# LPC55S69_MINI_B.net
KiCad netlist of a schematic drawn in Altium Designer
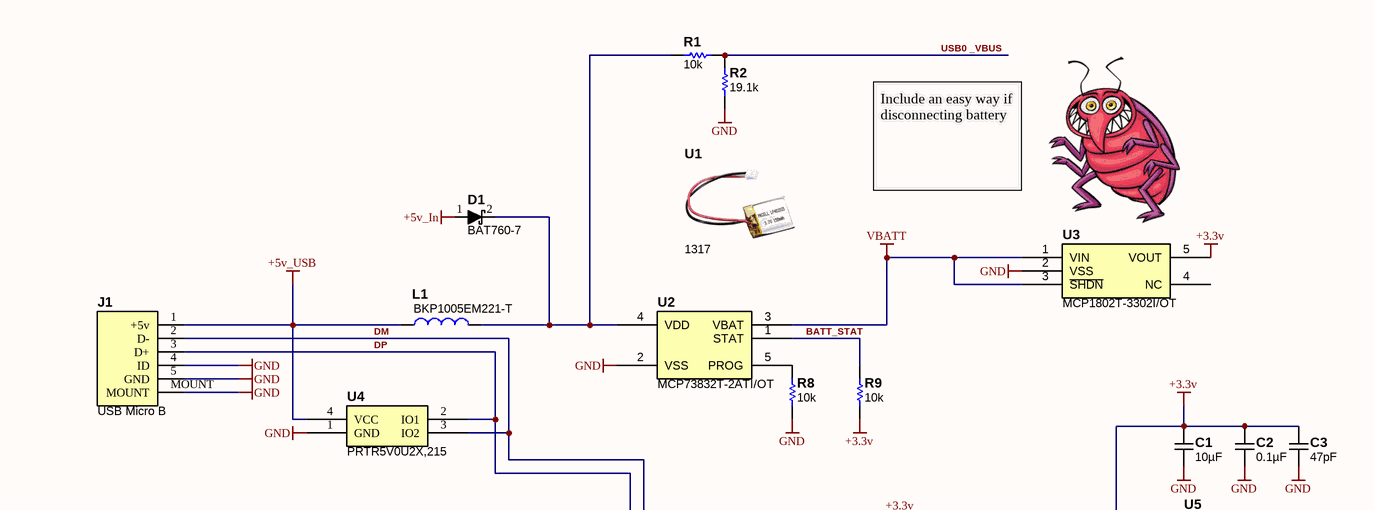
[diagram p0: LPC55S69_MINI [B].SchDoc, top left]
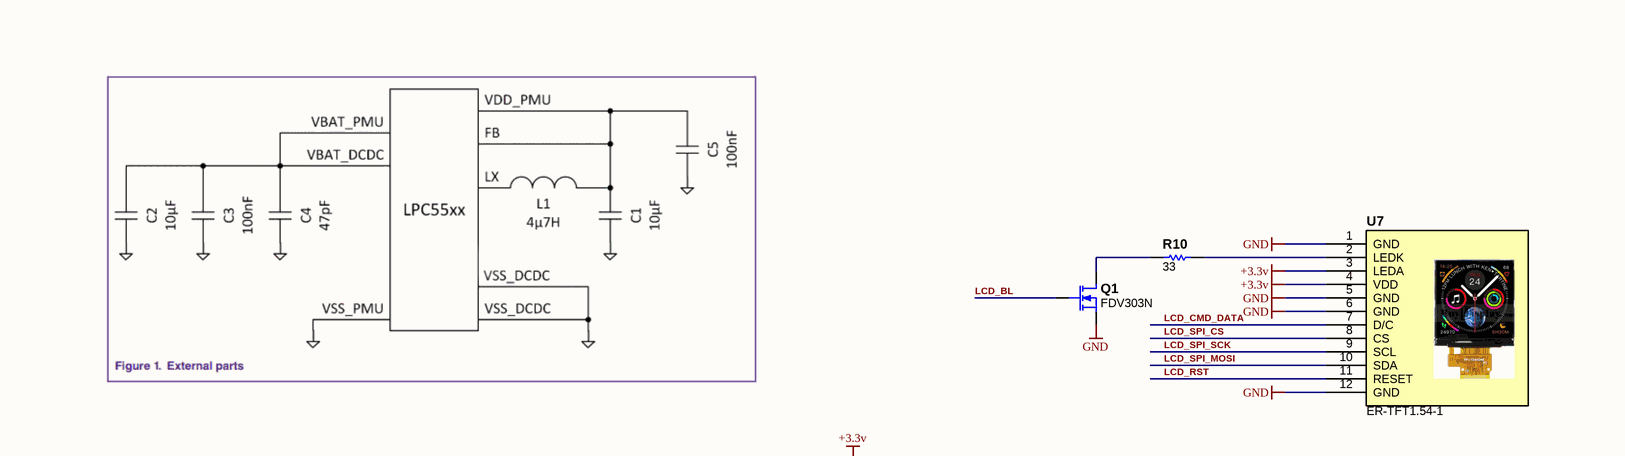
[diagram p1: LPC55S69_MINI [B].SchDoc, top right]
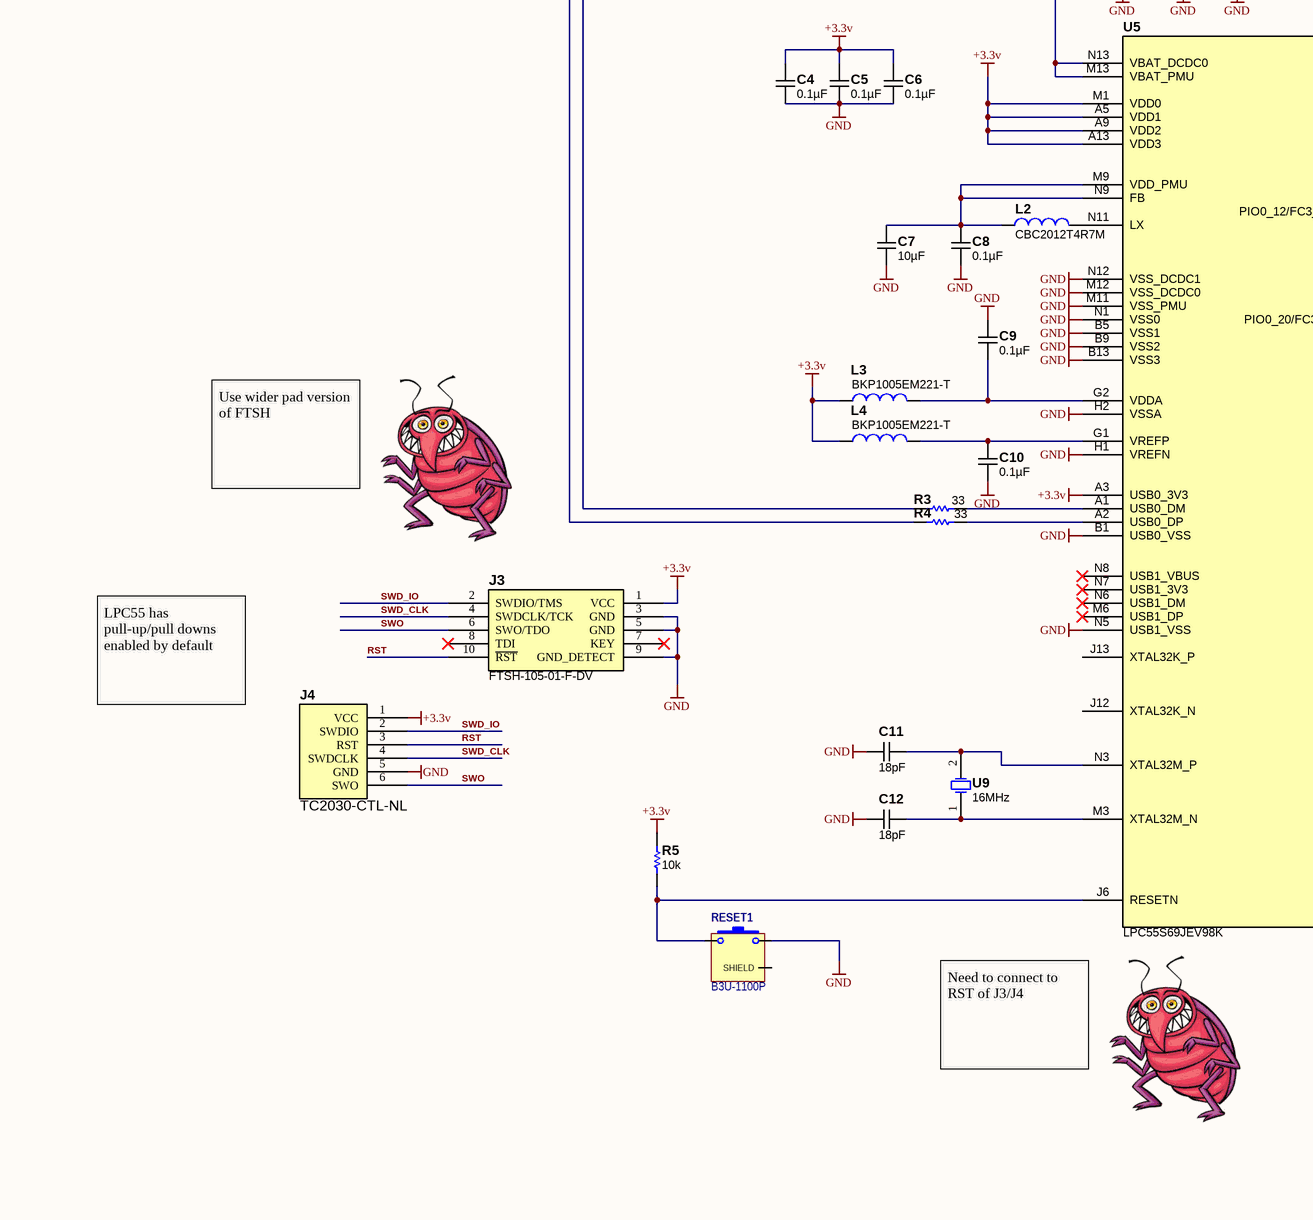
[diagram p2: LPC55S69_MINI [B].SchDoc, bottom left]
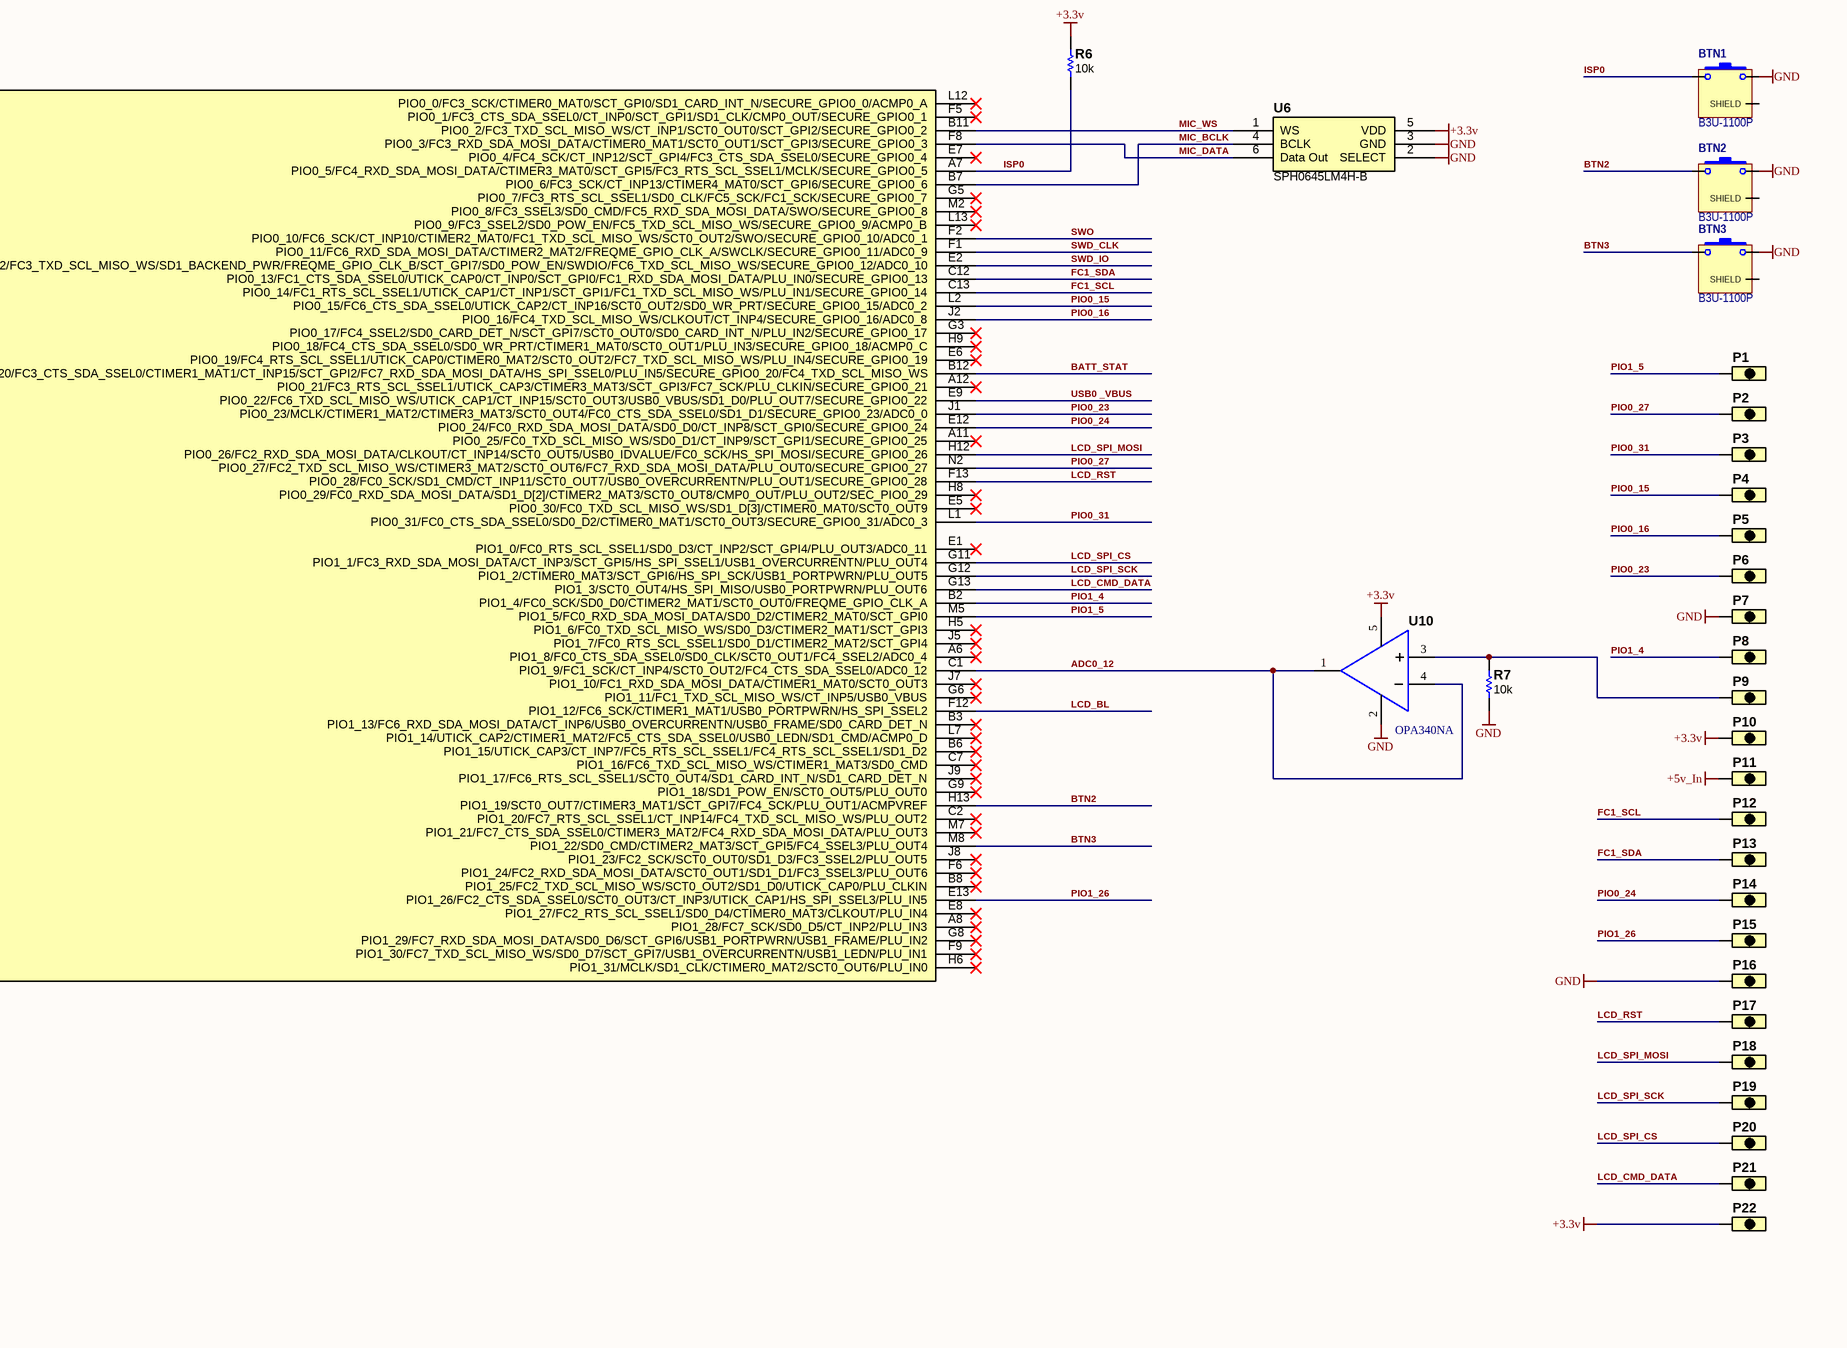
[diagram p3: LPC55S69_MINI [B].SchDoc, bottom right]

(export (version "E")
  (design (tool "Eeschema 10.0.6"))
  (components
    (comp (ref "BTN1")
      (value "B3U-1100P")
      (footprint "OMRON_B3U-1100P")
      (description "SWITCH TACTILE SPST-NO 0.05A 12V")
      (fields (field (name "MANUFACTURER") "Omron Electronics Inc-EMC Div"))
      (libsource (lib "Switches-N") (part "B3U-1100P"))
    )
    (comp (ref "BTN2")
      (value "B3U-1100P")
      (footprint "OMRON_B3U-1100P")
      (description "SWITCH TACTILE SPST-NO 0.05A 12V")
      (fields (field (name "MANUFACTURER") "Omron Electronics Inc-EMC Div"))
      (libsource (lib "Switches-N") (part "B3U-1100P"))
    )
    (comp (ref "BTN3")
      (value "B3U-1100P")
      (footprint "OMRON_B3U-1100P")
      (description "SWITCH TACTILE SPST-NO 0.05A 12V")
      (fields (field (name "MANUFACTURER") "Omron Electronics Inc-EMC Div"))
      (libsource (lib "Switches-N") (part "B3U-1100P"))
    )
    (comp (ref "C1")
      (value "10µF")
      (footprint "C0805_1.45MM_MD")
      (description "CAP CER 10UF 6.3V X7R 0805")
      (fields
        (field (name "MANUFACTURER PART NUMBER") "CGA4J1X7R0J106K125AC")
        (field (name "MANUFACTURER") "TDK Corporation")
      )
      (libsource (lib "Capacitors - TDK- AEC-Q200") (part "C_2P_NP"))
    )
    (comp (ref "C2")
      (value "0.1µF")
      (footprint "C0402_0.55MM_MD")
      (description "CAP CER 0.1UF 16V X7R 0402")
      (fields
        (field (name "MANUFACTURER PART NUMBER") "CGA2B1X7R1C104K050BC")
        (field (name "MANUFACTURER") "TDK Corporation")
      )
      (libsource (lib "Capacitors - TDK- AEC-Q200") (part "C_2P_NP"))
    )
    (comp (ref "C3")
      (value "47pF")
      (footprint "C0402_0.55MM_MD")
      (description "CAP CER 47PF 50V C0G 0402")
      (fields
        (field (name "MANUFACTURER PART NUMBER") "CGA2B2C0G1H470J050BA")
        (field (name "MANUFACTURER") "TDK Corporation")
      )
      (libsource (lib "Capacitors - TDK- AEC-Q200") (part "C_2P_NP"))
    )
    (comp (ref "C4")
      (value "0.1µF")
      (footprint "C0402_0.55MM_MD")
      (description "CAP CER 0.1UF 16V X7R 0402")
      (fields
        (field (name "MANUFACTURER PART NUMBER") "CGA2B1X7R1C104K050BC")
        (field (name "MANUFACTURER") "TDK Corporation")
      )
      (libsource (lib "Capacitors - TDK- AEC-Q200") (part "C_2P_NP"))
    )
    (comp (ref "C5")
      (value "0.1µF")
      (footprint "C0402_0.55MM_MD")
      (description "CAP CER 0.1UF 16V X7R 0402")
      (fields
        (field (name "MANUFACTURER PART NUMBER") "CGA2B1X7R1C104K050BC")
        (field (name "MANUFACTURER") "TDK Corporation")
      )
      (libsource (lib "Capacitors - TDK- AEC-Q200") (part "C_2P_NP"))
    )
    (comp (ref "C6")
      (value "0.1µF")
      (footprint "C0402_0.55MM_MD")
      (description "CAP CER 0.1UF 16V X7R 0402")
      (fields
        (field (name "MANUFACTURER PART NUMBER") "CGA2B1X7R1C104K050BC")
        (field (name "MANUFACTURER") "TDK Corporation")
      )
      (libsource (lib "Capacitors - TDK- AEC-Q200") (part "C_2P_NP"))
    )
    (comp (ref "C7")
      (value "10µF")
      (footprint "C0805_1.45MM_MD")
      (description "CAP CER 10UF 6.3V X7R 0805")
      (fields
        (field (name "MANUFACTURER PART NUMBER") "CGA4J1X7R0J106K125AC")
        (field (name "MANUFACTURER") "TDK Corporation")
      )
      (libsource (lib "Capacitors - TDK- AEC-Q200") (part "C_2P_NP"))
    )
    (comp (ref "C8")
      (value "0.1µF")
      (footprint "C0402_0.55MM_MD")
      (description "CAP CER 0.1UF 16V X7R 0402")
      (fields
        (field (name "MANUFACTURER PART NUMBER") "CGA2B1X7R1C104K050BC")
        (field (name "MANUFACTURER") "TDK Corporation")
      )
      (libsource (lib "Capacitors - TDK- AEC-Q200") (part "C_2P_NP"))
    )
    (comp (ref "C9")
      (value "0.1µF")
      (footprint "C0402_0.55MM_MD")
      (description "CAP CER 0.1UF 16V X7R 0402")
      (fields
        (field (name "MANUFACTURER PART NUMBER") "CGA2B1X7R1C104K050BC")
        (field (name "MANUFACTURER") "TDK Corporation")
      )
      (libsource (lib "Capacitors - TDK- AEC-Q200") (part "C_2P_NP"))
    )
    (comp (ref "C10")
      (value "0.1µF")
      (footprint "C0402_0.55MM_MD")
      (description "CAP CER 0.1UF 16V X7R 0402")
      (fields
        (field (name "MANUFACTURER PART NUMBER") "CGA2B1X7R1C104K050BC")
        (field (name "MANUFACTURER") "TDK Corporation")
      )
      (libsource (lib "Capacitors - TDK- AEC-Q200") (part "C_2P_NP"))
    )
    (comp (ref "C11")
      (value "18pF")
      (footprint "C0402_0.55MM_MD")
      (description "CAP CER 18PF 50V C0G 0402")
      (fields
        (field (name "MANUFACTURER PART NUMBER") "CGA2B2C0G1H180J050BA")
        (field (name "MANUFACTURER") "TDK Corporation")
      )
      (libsource (lib "Capacitors - TDK- AEC-Q200") (part "C_2P_NP"))
    )
    (comp (ref "C12")
      (value "18pF")
      (footprint "C0402_0.55MM_MD")
      (description "CAP CER 18PF 50V C0G 0402")
      (fields
        (field (name "MANUFACTURER PART NUMBER") "CGA2B2C0G1H180J050BA")
        (field (name "MANUFACTURER") "TDK Corporation")
      )
      (libsource (lib "Capacitors - TDK- AEC-Q200") (part "C_2P_NP"))
    )
    (comp (ref "D1")
      (value "BAT760-7")
      (footprint "D_SOD-323_P")
      (description "DIODE SCHOTTKY 30V 1A SOD323")
      (fields (field (name "MANUFACTURER") "Diodes Inc"))
      (libsource (lib "Diodes") (part "DS_1A_2C"))
    )
    (comp (ref "J1")
      (value "USB Micro B")
      (footprint "10103594-0001LF")
      (description "CONN RCPT STD MICRO USB TYPE B")
      (fields (field (name "MANUFACTURER") "FCI") (field (name "MANUFACTURER PART NUMBER") "10103594-0001LF"))
      (libsource (lib "eConnector_USB") (part "10103594-0001LF"))
    )
    (comp (ref "J3")
      (value "FTSH-105-01-F-DV")
      (footprint "FTSH-105-04-F-DV - HD - NO_STEP")
      (description "SAMTEC - FTSH-105-01-F-DV - .050 X .050")
      (fields (field (name "MANUFACTURER") "SAMTEC"))
      (libsource (lib "eConnector") (part "CORTEX-DEBUG"))
    )
    (comp (ref "J4")
      (value "TC2030‐CTL‐NL")
      (footprint "TC2030 NO LATCH")
      (description "Tag Connect Pads - No latching Clips - ARM")
      (libsource (lib "eConnector") (part "TC2030‐CTL‐NL"))
    )
    (comp (ref "L1")
      (value "BKP1005EM221-T")
      (footprint "C0402_HD")
      (description "FERRITE BEAD 220 OHM 0402 1LN")
      (fields (field (name "MANUFACTURER") "Taiyo Yuden"))
      (libsource (lib "eInductor") (part "BKP1005EM221-T"))
    )
    (comp (ref "L2")
      (value "CBC2012T4R7M")
      (footprint "C0805_1.45MM_MD")
      (description "FIXED IND 4.7UH 520MA 650 MOHM")
      (fields (field (name "MANUFACTURER") "Taiyo Yuden") (field (name "TOLERANCE") "20%"))
      (libsource (lib "eInductor") (part "CBC2012T4R7M"))
    )
    (comp (ref "L3")
      (value "BKP1005EM221-T")
      (footprint "C0402_HD")
      (description "FERRITE BEAD 220 OHM 0402 1LN")
      (fields (field (name "MANUFACTURER") "Taiyo Yuden"))
      (libsource (lib "eInductor") (part "BKP1005EM221-T"))
    )
    (comp (ref "L4")
      (value "BKP1005EM221-T")
      (footprint "C0402_HD")
      (description "FERRITE BEAD 220 OHM 0402 1LN")
      (fields (field (name "MANUFACTURER") "Taiyo Yuden"))
      (libsource (lib "eInductor") (part "BKP1005EM221-T"))
    )
    (comp (ref "P1")
      (value "~")
      (footprint "CASTELLATED")
      (libsource (lib "eConnector") (part "CASTELLATED"))
    )
    (comp (ref "P2")
      (value "~")
      (footprint "CASTELLATED")
      (libsource (lib "eConnector") (part "CASTELLATED"))
    )
    (comp (ref "P3")
      (value "~")
      (footprint "CASTELLATED")
      (libsource (lib "eConnector") (part "CASTELLATED"))
    )
    (comp (ref "P4")
      (value "~")
      (footprint "CASTELLATED")
      (libsource (lib "eConnector") (part "CASTELLATED"))
    )
    (comp (ref "P5")
      (value "~")
      (footprint "CASTELLATED")
      (libsource (lib "eConnector") (part "CASTELLATED"))
    )
    (comp (ref "P6")
      (value "~")
      (footprint "CASTELLATED")
      (libsource (lib "eConnector") (part "CASTELLATED"))
    )
    (comp (ref "P7")
      (value "~")
      (footprint "CASTELLATED")
      (libsource (lib "eConnector") (part "CASTELLATED"))
    )
    (comp (ref "P8")
      (value "~")
      (footprint "CASTELLATED")
      (libsource (lib "eConnector") (part "CASTELLATED"))
    )
    (comp (ref "P9")
      (value "~")
      (footprint "CASTELLATED")
      (libsource (lib "eConnector") (part "CASTELLATED"))
    )
    (comp (ref "P10")
      (value "~")
      (footprint "CASTELLATED")
      (libsource (lib "eConnector") (part "CASTELLATED"))
    )
    (comp (ref "P11")
      (value "~")
      (footprint "CASTELLATED")
      (libsource (lib "eConnector") (part "CASTELLATED"))
    )
    (comp (ref "P12")
      (value "~")
      (footprint "CASTELLATED")
      (libsource (lib "eConnector") (part "CASTELLATED"))
    )
    (comp (ref "P13")
      (value "~")
      (footprint "CASTELLATED")
      (libsource (lib "eConnector") (part "CASTELLATED"))
    )
    (comp (ref "P14")
      (value "~")
      (footprint "CASTELLATED")
      (libsource (lib "eConnector") (part "CASTELLATED"))
    )
    (comp (ref "P15")
      (value "~")
      (footprint "CASTELLATED")
      (libsource (lib "eConnector") (part "CASTELLATED"))
    )
    (comp (ref "P16")
      (value "~")
      (footprint "CASTELLATED")
      (libsource (lib "eConnector") (part "CASTELLATED"))
    )
    (comp (ref "P17")
      (value "~")
      (footprint "CASTELLATED")
      (libsource (lib "eConnector") (part "CASTELLATED"))
    )
    (comp (ref "P18")
      (value "~")
      (footprint "CASTELLATED")
      (libsource (lib "eConnector") (part "CASTELLATED"))
    )
    (comp (ref "P19")
      (value "~")
      (footprint "CASTELLATED")
      (libsource (lib "eConnector") (part "CASTELLATED"))
    )
    (comp (ref "P20")
      (value "~")
      (footprint "CASTELLATED")
      (libsource (lib "eConnector") (part "CASTELLATED"))
    )
    (comp (ref "P21")
      (value "~")
      (footprint "CASTELLATED")
      (libsource (lib "eConnector") (part "CASTELLATED"))
    )
    (comp (ref "P22")
      (value "~")
      (footprint "CASTELLATED")
      (libsource (lib "eConnector") (part "CASTELLATED"))
    )
    (comp (ref "Q1")
      (value "FDV303N")
      (footprint "SOT-23")
      (description "MOSFET N-CH 25V 680MA SOT-23")
      (fields (field (name "MANUFACTURER") "Fairchild Semiconductor") (field (name "SOURCE") "Digikey"))
      (libsource (lib "eTransistor") (part "FDV303N"))
    )
    (comp (ref "R1")
      (value "10k")
      (footprint "R0402_0.40MM_MD")
      (description "RES 10K OHM 1/10W 1% 0402 SMD")
      (fields
        (field (name "MANUFACTURER PART NUMBER") "ERJ-2RKF1002X")
        (field (name "MANUFACTURER") "Panasonic Electronic Components")
      )
      (libsource (lib "Resistors - Panasonic - AEC-Q200") (part "R_2P"))
    )
    (comp (ref "R2")
      (value "19.1k")
      (footprint "R0402_0.40MM_MD")
      (description "RES 19.1K OHM 1/10W 1% 0402 SMD")
      (fields
        (field (name "MANUFACTURER PART NUMBER") "ERJ-2RKF1912X")
        (field (name "MANUFACTURER") "Panasonic Electronic Components")
      )
      (libsource (lib "Resistors - Panasonic - AEC-Q200") (part "R_2P"))
    )
    (comp (ref "R3")
      (value "33")
      (footprint "R0603_0.55MM_MD")
      (description "RES 33 OHM 1/10W 1% 0603 SMD")
      (fields
        (field (name "MANUFACTURER PART NUMBER") "ERJ-3EKF33R0V")
        (field (name "MANUFACTURER") "Panasonic Electronic Components")
      )
      (libsource (lib "Resistors - Panasonic - AEC-Q200") (part "R_2P"))
    )
    (comp (ref "R4")
      (value "33")
      (footprint "R0603_0.55MM_MD")
      (description "RES 33 OHM 1/10W 1% 0603 SMD")
      (fields
        (field (name "MANUFACTURER PART NUMBER") "ERJ-3EKF33R0V")
        (field (name "MANUFACTURER") "Panasonic Electronic Components")
      )
      (libsource (lib "Resistors - Panasonic - AEC-Q200") (part "R_2P"))
    )
    (comp (ref "R5")
      (value "10k")
      (footprint "R0402_0.40MM_MD")
      (description "RES 10K OHM 1/10W 1% 0402 SMD")
      (fields
        (field (name "MANUFACTURER PART NUMBER") "ERJ-2RKF1002X")
        (field (name "MANUFACTURER") "Panasonic Electronic Components")
      )
      (libsource (lib "Resistors - Panasonic - AEC-Q200") (part "R_2P"))
    )
    (comp (ref "R6")
      (value "10k")
      (footprint "R0402_0.40MM_MD")
      (description "RES 10K OHM 1/10W 1% 0402 SMD")
      (fields
        (field (name "MANUFACTURER PART NUMBER") "ERJ-2RKF1002X")
        (field (name "MANUFACTURER") "Panasonic Electronic Components")
      )
      (libsource (lib "Resistors - Panasonic - AEC-Q200") (part "R_2P"))
    )
    (comp (ref "R7")
      (value "10k")
      (footprint "R0402_0.40MM_MD")
      (description "RES 10K OHM 1/10W 1% 0402 SMD")
      (fields
        (field (name "MANUFACTURER PART NUMBER") "ERJ-2RKF1002X")
        (field (name "MANUFACTURER") "Panasonic Electronic Components")
      )
      (libsource (lib "Resistors - Panasonic - AEC-Q200") (part "R_2P"))
    )
    (comp (ref "R8")
      (value "10k")
      (footprint "R0402_0.40MM_MD")
      (description "RES 10K OHM 1/10W 1% 0402 SMD")
      (fields
        (field (name "MANUFACTURER PART NUMBER") "ERJ-2RKF1002X")
        (field (name "MANUFACTURER") "Panasonic Electronic Components")
      )
      (libsource (lib "Resistors - Panasonic - AEC-Q200") (part "R_2P"))
    )
    (comp (ref "R9")
      (value "10k")
      (footprint "R0402_0.40MM_MD")
      (description "RES 10K OHM 1/10W 1% 0402 SMD")
      (fields
        (field (name "MANUFACTURER PART NUMBER") "ERJ-2RKF1002X")
        (field (name "MANUFACTURER") "Panasonic Electronic Components")
      )
      (libsource (lib "Resistors - Panasonic - AEC-Q200") (part "R_2P"))
    )
    (comp (ref "R10")
      (value "33")
      (footprint "R0603_0.55MM_MD")
      (description "RES 33 OHM 1/10W 1% 0603 SMD")
      (fields
        (field (name "MANUFACTURER PART NUMBER") "ERJ-3EKF33R0V")
        (field (name "MANUFACTURER") "Panasonic Electronic Components")
      )
      (libsource (lib "Resistors - Panasonic - AEC-Q200") (part "R_2P"))
    )
    (comp (ref "RESET1")
      (value "B3U-1100P")
      (footprint "OMRON_B3U-1100P")
      (description "SWITCH TACTILE SPST-NO 0.05A 12V")
      (fields (field (name "MANUFACTURER") "Omron Electronics Inc-EMC Div"))
      (libsource (lib "Switches-N") (part "B3U-1100P"))
    )
    (comp (ref "U1")
      (value "1317")
      (footprint "LIPO-150MAH")
      (description "FLORA LI-PO BATTERY 3.7V 150MAH")
      (fields (field (name "MANUFACTURER") "Adafruit Industries"))
      (libsource (lib "eBattery") (part "1317"))
    )
    (comp (ref "U2")
      (value "MCP73832T-2ATI/OT")
      (footprint "SOT23-5")
      (description "Charge Controller Li-Ion/Li-Pol 15mA to 500mA 4.2V 5-Pin SOT-23 T/R")
      (fields (field (name "MANUFACTURER") "Microchip"))
      (libsource (lib "eIC") (part "MCP73832T-2ATI/OT"))
    )
    (comp (ref "U3")
      (value "MCP1802T-3302I/OT")
      (footprint "SOT23-5")
      (description "IC REG LINEAR 3.3V 300MA SOT23-5")
      (fields (field (name "MANUFACTURER") "Microchip"))
      (libsource (lib "eIC_Regulator") (part "MCP1802T-3302I/OT"))
    )
    (comp (ref "U4")
      (value "PRTR5V0U2X,215")
      (footprint "SOT143B")
      (description "TVS DIODE 5.5VWM SOT143B")
      (fields (field (name "MANUFACTURER") "NXP Semiconductors"))
      (libsource (lib "eDiode") (part "PRTR5V0U2X,215"))
    )
    (comp (ref "U5")
      (value "LPC55S69JEV98K")
      (footprint "98-VFBGA")
      (description "IC MCU 100MHZ CORTEX M33 DUAL")
      (fields (field (name "MANUFACTURER") "NXP Semiconductors"))
      (libsource (lib "eIC") (part "LPC55S69JEV98K"))
    )
    (comp (ref "U6")
      (value "SPH0645LM4H-B")
      (footprint "SPH0645LM4H-B")
      (fields (field (name "MANUFACTURER") "Knowles Acoustics"))
      (libsource (lib "eAudio") (part "SPH0645LM4H-B"))
    )
    (comp (ref "U7")
      (value "ER-TFT1.54-1")
      (footprint "ER-TFT1.54-1")
      (description "1.54\" 240x240 IPS Display")
      (fields (field (name "MANUFACTURER") "Buy Display"))
      (libsource (lib "eDisplay") (part "ER-TFT1.54-1"))
    )
    (comp (ref "U9")
      (value "16MHz")
      (footprint "ABM3")
      (description "Crystal 16MHz ±20ppm (Tol) ±50ppm (Stability) 18pF FUND 50Ohm 2-Pin CSMD T/R")
      (fields
        (field (name "MANUFACTURER") "Abracon")
        (field (name "MANUFACTURER PART NUMBER") "ABM3-16.000MHZ-B2-T")
      )
      (libsource (lib "eCrystal") (part "ABM3-16.000MHZ-B2-T"))
    )
    (comp (ref "U10")
      (value "OPA340NA")
      (footprint "SOT95P245X145-5L")
      (description "IC SINGLE SUPPLY OPAMP SOT-23-5")
      (fields
        (field (name "MANUFACTURER") "Texas Instruments")
        (field (name "MANUFACTURER PART NUMBER") "OPA340NA/250")
        (field (name "SOURCE") "Digikey")
      )
      (libsource (lib "eOPAMP") (part "OPA340"))
    )
  )
  (nets
    (net (code "1") (name "+3.3v") (class "Default")
      (node (ref "C1") (pin "2") (pinfunction "1_2") (pintype "passive"))
      (node (ref "C2") (pin "2") (pinfunction "1_2") (pintype "passive"))
      (node (ref "C3") (pin "2") (pinfunction "1_2") (pintype "passive"))
      (node (ref "C4") (pin "2") (pinfunction "1_2") (pintype "passive"))
      (node (ref "C5") (pin "2") (pinfunction "1_2") (pintype "passive"))
      (node (ref "C6") (pin "2") (pinfunction "1_2") (pintype "passive"))
      (node (ref "J3") (pin "1") (pinfunction "VCC_1") (pintype "passive"))
      (node (ref "J4") (pin "1") (pinfunction "VCC_1") (pintype "passive"))
      (node (ref "L3") (pin "1") (pinfunction "1_1") (pintype "passive"))
      (node (ref "L4") (pin "1") (pinfunction "1_1") (pintype "passive"))
      (node (ref "P10") (pin "1") (pinfunction "1_1") (pintype "passive"))
      (node (ref "P22") (pin "1") (pinfunction "1_1") (pintype "passive"))
      (node (ref "R5") (pin "2") (pinfunction "2_2") (pintype "passive"))
      (node (ref "R6") (pin "2") (pinfunction "2_2") (pintype "passive"))
      (node (ref "R9") (pin "1") (pinfunction "1_1") (pintype "passive"))
      (node (ref "U10") (pin "5") (pinfunction "VCC_5") (pintype "passive"))
      (node (ref "U3") (pin "5") (pinfunction "VOUT_5") (pintype "passive"))
      (node (ref "U5") (pin "A13") (pinfunction "VDD3_A13") (pintype "passive"))
      (node (ref "U5") (pin "A3") (pinfunction "USB0_3V3_A3") (pintype "passive"))
      (node (ref "U5") (pin "A5") (pinfunction "VDD1_A5") (pintype "passive"))
      (node (ref "U5") (pin "A9") (pinfunction "VDD2_A9") (pintype "passive"))
      (node (ref "U5") (pin "M1") (pinfunction "VDD0_M1") (pintype "passive"))
      (node (ref "U5") (pin "M13") (pinfunction "VBAT_PMU_M13") (pintype "passive"))
      (node (ref "U5") (pin "N13") (pinfunction "VBAT_DCDC0_N13") (pintype "passive"))
      (node (ref "U6") (pin "5") (pinfunction "VDD_5") (pintype "passive"))
      (node (ref "U7") (pin "3") (pinfunction "LEDA_3") (pintype "passive"))
      (node (ref "U7") (pin "4") (pinfunction "VDD_4") (pintype "passive"))
    )
    (net (code "2") (name "+5v_In") (class "Default")
      (node (ref "D1") (pin "1") (pinfunction "A_1") (pintype "passive"))
      (node (ref "P11") (pin "1") (pinfunction "1_1") (pintype "passive"))
    )
    (net (code "3") (name "+5v_USB") (class "Default")
      (node (ref "J1") (pin "1") (pinfunction "+5v_1") (pintype "passive"))
      (node (ref "L1") (pin "1") (pinfunction "1_1") (pintype "passive"))
      (node (ref "U4") (pin "4") (pinfunction "VCC_4") (pintype "passive"))
    )
    (net (code "4") (name "/ADC0_12") (class "Default")
      (node (ref "U10") (pin "1") (pinfunction "OUT_1") (pintype "passive"))
      (node (ref "U10") (pin "4") (pinfunction "-_4") (pintype "passive"))
      (node (ref "U5") (pin "C1") (pinfunction "PIO1_9/FC1_SCK/CT_INP4/SCT0_OUT2/FC4_CTS_SDA_SSEL0/ADC0_12_C1") (pintype "passive"))
    )
    (net (code "5") (name "/BATT_STAT") (class "Default")
      (node (ref "R9") (pin "2") (pinfunction "2_2") (pintype "passive"))
      (node (ref "U2") (pin "1") (pinfunction "STAT_1") (pintype "passive"))
      (node (ref "U5") (pin "B12") (pinfunction "PIO0_20/FC3_CTS_SDA_SSEL0/CTIMER1_MAT1/CT_INP15/SCT_GPI2/FC7_RXD_SDA_MOSI_DATA/HS_SPI_SSEL0/PLU_IN5/SECURE_GPIO0_20/FC4_TXD_SCL_MISO_WS_B12") (pintype "passive"))
    )
    (net (code "6") (name "/BTN2") (class "Default")
      (node (ref "BTN2") (pin "2") (pinfunction "2_2") (pintype "passive"))
      (node (ref "U5") (pin "H13") (pinfunction "PIO1_19/SCT0_OUT7/CTIMER3_MAT1/SCT_GPI7/FC4_SCK/PLU_OUT1/ACMPVREF_H13") (pintype "passive"))
    )
    (net (code "7") (name "/BTN3") (class "Default")
      (node (ref "BTN3") (pin "2") (pinfunction "2_2") (pintype "passive"))
      (node (ref "U5") (pin "M8") (pinfunction "PIO1_22/SD0_CMD/CTIMER2_MAT3/SCT_GPI5/FC4_SSEL3/PLU_OUT4_M8") (pintype "passive"))
    )
    (net (code "8") (name "/DM") (class "Default")
      (node (ref "J1") (pin "2") (pinfunction "D-_2") (pintype "passive"))
      (node (ref "R3") (pin "1") (pinfunction "1_1") (pintype "passive"))
      (node (ref "U4") (pin "3") (pinfunction "IO2_3") (pintype "passive"))
    )
    (net (code "9") (name "/DP") (class "Default")
      (node (ref "J1") (pin "3") (pinfunction "D+_3") (pintype "passive"))
      (node (ref "R4") (pin "1") (pinfunction "1_1") (pintype "passive"))
      (node (ref "U4") (pin "2") (pinfunction "IO1_2") (pintype "passive"))
    )
    (net (code "10") (name "/FC1_SCL") (class "Default")
      (node (ref "P12") (pin "1") (pinfunction "1_1") (pintype "passive"))
      (node (ref "U5") (pin "C13") (pinfunction "PIO0_14/FC1_RTS_SCL_SSEL1/UTICK_CAP1/CT_INP1/SCT_GPI1/FC1_TXD_SCL_MISO_WS/PLU_IN1/SECURE_GPIO0_14_C13") (pintype "passive"))
    )
    (net (code "11") (name "/FC1_SDA") (class "Default")
      (node (ref "P13") (pin "1") (pinfunction "1_1") (pintype "passive"))
      (node (ref "U5") (pin "C12") (pinfunction "PIO0_13/FC1_CTS_SDA_SSEL0/UTICK_CAP0/CT_INP0/SCT_GPI0/FC1_RXD_SDA_MOSI_DATA/PLU_IN0/SECURE_GPIO0_13_C12") (pintype "passive"))
    )
    (net (code "12") (name "/ISP0") (class "Default")
      (node (ref "BTN1") (pin "2") (pinfunction "2_2") (pintype "passive"))
      (node (ref "R6") (pin "1") (pinfunction "1_1") (pintype "passive"))
      (node (ref "U5") (pin "A7") (pinfunction "PIO0_5/FC4_RXD_SDA_MOSI_DATA/CTIMER3_MAT0/SCT_GPI5/FC3_RTS_SCL_SSEL1/MCLK/SECURE_GPIO0_5_A7") (pintype "passive"))
    )
    (net (code "13") (name "/LCD_BL") (class "Default")
      (node (ref "Q1") (pin "1") (pinfunction "G_1") (pintype "passive"))
      (node (ref "U5") (pin "F12") (pinfunction "PIO1_12/FC6_SCK/CTIMER1_MAT1/USB0_PORTPWRN/HS_SPI_SSEL2_F12") (pintype "passive"))
    )
    (net (code "14") (name "/LCD_CMD_DATA") (class "Default")
      (node (ref "P21") (pin "1") (pinfunction "1_1") (pintype "passive"))
      (node (ref "U5") (pin "G13") (pinfunction "PIO1_3/SCT0_OUT4/HS_SPI_MISO/USB0_PORTPWRN/PLU_OUT6_G13") (pintype "passive"))
      (node (ref "U7") (pin "7") (pinfunction "D/C_7") (pintype "passive"))
    )
    (net (code "15") (name "/LCD_RST") (class "Default")
      (node (ref "P17") (pin "1") (pinfunction "1_1") (pintype "passive"))
      (node (ref "U5") (pin "F13") (pinfunction "PIO0_28/FC0_SCK/SD1_CMD/CT_INP11/SCT0_OUT7/USB0_OVERCURRENTN/PLU_OUT1/SECURE_GPIO0_28_F13") (pintype "passive"))
      (node (ref "U7") (pin "11") (pinfunction "RESET_11") (pintype "passive"))
    )
    (net (code "16") (name "/LCD_SPI_CS") (class "Default")
      (node (ref "P20") (pin "1") (pinfunction "1_1") (pintype "passive"))
      (node (ref "U5") (pin "G11") (pinfunction "PIO1_1/FC3_RXD_SDA_MOSI_DATA/CT_INP3/SCT_GPI5/HS_SPI_SSEL1/USB1_OVERCURRENTN/PLU_OUT4_G11") (pintype "passive"))
      (node (ref "U7") (pin "8") (pinfunction "CS_8") (pintype "passive"))
    )
    (net (code "17") (name "/LCD_SPI_MOSI") (class "Default")
      (node (ref "P18") (pin "1") (pinfunction "1_1") (pintype "passive"))
      (node (ref "U5") (pin "H12") (pinfunction "PIO0_26/FC2_RXD_SDA_MOSI_DATA/CLKOUT/CT_INP14/SCT0_OUT5/USB0_IDVALUE/FC0_SCK/HS_SPI_MOSI/SECURE_GPIO0_26_H12") (pintype "passive"))
      (node (ref "U7") (pin "10") (pinfunction "SDA_10") (pintype "passive"))
    )
    (net (code "18") (name "/LCD_SPI_SCK") (class "Default")
      (node (ref "P19") (pin "1") (pinfunction "1_1") (pintype "passive"))
      (node (ref "U5") (pin "G12") (pinfunction "PIO1_2/CTIMER0_MAT3/SCT_GPI6/HS_SPI_SCK/USB1_PORTPWRN/PLU_OUT5_G12") (pintype "passive"))
      (node (ref "U7") (pin "9") (pinfunction "SCL_9") (pintype "passive"))
    )
    (net (code "19") (name "/MIC_BCLK") (class "Default")
      (node (ref "U5") (pin "B7") (pinfunction "PIO0_6/FC3_SCK/CT_INP13/CTIMER4_MAT0/SCT_GPI6/SECURE_GPIO0_6_B7") (pintype "passive"))
      (node (ref "U6") (pin "4") (pinfunction "BCLK_4") (pintype "passive"))
    )
    (net (code "20") (name "/MIC_DATA") (class "Default")
      (node (ref "U5") (pin "F8") (pinfunction "PIO0_3/FC3_RXD_SDA_MOSI_DATA/CTIMER0_MAT1/SCT0_OUT1/SCT_GPI3/SECURE_GPIO0_3_F8") (pintype "passive"))
      (node (ref "U6") (pin "6") (pinfunction "Data_Out_6") (pintype "passive"))
    )
    (net (code "21") (name "/MIC_WS") (class "Default")
      (node (ref "U5") (pin "B11") (pinfunction "PIO0_2/FC3_TXD_SCL_MISO_WS/CT_INP1/SCT0_OUT0/SCT_GPI2/SECURE_GPIO0_2_B11") (pintype "passive"))
      (node (ref "U6") (pin "1") (pinfunction "WS_1") (pintype "passive"))
    )
    (net (code "22") (name "/PIO0_15") (class "Default")
      (node (ref "P4") (pin "1") (pinfunction "1_1") (pintype "passive"))
      (node (ref "U5") (pin "L2") (pinfunction "PIO0_15/FC6_CTS_SDA_SSEL0/UTICK_CAP2/CT_INP16/SCT0_OUT2/SD0_WR_PRT/SECURE_GPIO0_15/ADC0_2_L2") (pintype "passive"))
    )
    (net (code "23") (name "/PIO0_16") (class "Default")
      (node (ref "P5") (pin "1") (pinfunction "1_1") (pintype "passive"))
      (node (ref "U5") (pin "J2") (pinfunction "PIO0_16/FC4_TXD_SCL_MISO_WS/CLKOUT/CT_INP4/SECURE_GPIO0_16/ADC0_8_J2") (pintype "passive"))
    )
    (net (code "24") (name "/PIO0_23") (class "Default")
      (node (ref "P6") (pin "1") (pinfunction "1_1") (pintype "passive"))
      (node (ref "U5") (pin "J1") (pinfunction "PIO0_23/MCLK/CTIMER1_MAT2/CTIMER3_MAT3/SCT0_OUT4/FC0_CTS_SDA_SSEL0/SD1_D1/SECURE_GPIO0_23/ADC0_0_J1") (pintype "passive"))
    )
    (net (code "25") (name "/PIO0_24") (class "Default")
      (node (ref "P14") (pin "1") (pinfunction "1_1") (pintype "passive"))
      (node (ref "U5") (pin "E12") (pinfunction "PIO0_24/FC0_RXD_SDA_MOSI_DATA/SD0_D0/CT_INP8/SCT_GPI0/SECURE_GPIO0_24_E12") (pintype "passive"))
    )
    (net (code "26") (name "/PIO0_27") (class "Default")
      (node (ref "P2") (pin "1") (pinfunction "1_1") (pintype "passive"))
      (node (ref "U5") (pin "N2") (pinfunction "PIO0_27/FC2_TXD_SCL_MISO_WS/CTIMER3_MAT2/SCT0_OUT6/FC7_RXD_SDA_MOSI_DATA/PLU_OUT0/SECURE_GPIO0_27_N2") (pintype "passive"))
    )
    (net (code "27") (name "/PIO0_31") (class "Default")
      (node (ref "P3") (pin "1") (pinfunction "1_1") (pintype "passive"))
      (node (ref "U5") (pin "L1") (pinfunction "PIO0_31/FC0_CTS_SDA_SSEL0/SD0_D2/CTIMER0_MAT1/SCT0_OUT3/SECURE_GPIO0_31/ADC0_3_L1") (pintype "passive"))
    )
    (net (code "28") (name "/PIO1_4") (class "Default")
      (node (ref "P8") (pin "1") (pinfunction "1_1") (pintype "passive"))
      (node (ref "U5") (pin "B2") (pinfunction "PIO1_4/FC0_SCK/SD0_D0/CTIMER2_MAT1/SCT0_OUT0/FREQME_GPIO_CLK_A_B2") (pintype "passive"))
    )
    (net (code "29") (name "/PIO1_5") (class "Default")
      (node (ref "P1") (pin "1") (pinfunction "1_1") (pintype "passive"))
      (node (ref "U5") (pin "M5") (pinfunction "PIO1_5/FC0_RXD_SDA_MOSI_DATA/SD0_D2/CTIMER2_MAT0/SCT_GPI0_M5") (pintype "passive"))
    )
    (net (code "30") (name "/PIO1_26") (class "Default")
      (node (ref "P15") (pin "1") (pinfunction "1_1") (pintype "passive"))
      (node (ref "U5") (pin "E13") (pinfunction "PIO1_26/FC2_CTS_SDA_SSEL0/SCT0_OUT3/CT_INP3/UTICK_CAP1/HS_SPI_SSEL3/PLU_IN5_E13") (pintype "passive"))
    )
    (net (code "31") (name "/RST") (class "Default")
      (node (ref "J3") (pin "10") (pinfunction "~{RST}_10") (pintype "passive"))
      (node (ref "J4") (pin "3") (pinfunction "RST_3") (pintype "passive"))
    )
    (net (code "32") (name "/SWD_CLK") (class "Default")
      (node (ref "J3") (pin "4") (pinfunction "SWDCLK/TCK_4") (pintype "passive"))
      (node (ref "J4") (pin "4") (pinfunction "SWDCLK_4") (pintype "passive"))
      (node (ref "U5") (pin "F1") (pinfunction "PIO0_11/FC6_RXD_SDA_MOSI_DATA/CTIMER2_MAT2/FREQME_GPIO_CLK_A/SWCLK/SECURE_GPIO0_11/ADC0_9_F1") (pintype "passive"))
    )
    (net (code "33") (name "/SWD_IO") (class "Default")
      (node (ref "J3") (pin "2") (pinfunction "SWDIO/TMS_2") (pintype "passive"))
      (node (ref "J4") (pin "2") (pinfunction "SWDIO_2") (pintype "passive"))
      (node (ref "U5") (pin "E2") (pinfunction "PIO0_12/FC3_TXD_SCL_MISO_WS/SD1_BACKEND_PWR/FREQME_GPIO_CLK_B/SCT_GPI7/SD0_POW_EN/SWDIO/FC6_TXD_SCL_MISO_WS/SECURE_GPIO0_12/ADC0_10_E2") (pintype "passive"))
    )
    (net (code "34") (name "/SWO") (class "Default")
      (node (ref "J3") (pin "6") (pinfunction "SWO/TDO_6") (pintype "passive"))
      (node (ref "J4") (pin "6") (pinfunction "SWO_6") (pintype "passive"))
      (node (ref "U5") (pin "F2") (pinfunction "PIO0_10/FC6_SCK/CT_INP10/CTIMER2_MAT0/FC1_TXD_SCL_MISO_WS/SCT0_OUT2/SWO/SECURE_GPIO0_10/ADC0_1_F2") (pintype "passive"))
    )
    (net (code "35") (name "/USB0 _VBUS") (class "Default")
      (node (ref "R1") (pin "2") (pinfunction "2_2") (pintype "passive"))
      (node (ref "R2") (pin "2") (pinfunction "2_2") (pintype "passive"))
      (node (ref "U5") (pin "E9") (pinfunction "PIO0_22/FC6_TXD_SCL_MISO_WS/UTICK_CAP1/CT_INP15/SCT0_OUT3/USB0_VBUS/SD1_D0/PLU_OUT7/SECURE_GPIO0_22_E9") (pintype "passive"))
    )
    (net (code "36") (name "GND") (class "Default")
      (node (ref "BTN1") (pin "1") (pinfunction "1_1") (pintype "passive"))
      (node (ref "BTN2") (pin "1") (pinfunction "1_1") (pintype "passive"))
      (node (ref "BTN3") (pin "1") (pinfunction "1_1") (pintype "passive"))
      (node (ref "C1") (pin "1") (pinfunction "1_1") (pintype "passive"))
      (node (ref "C10") (pin "1") (pinfunction "1_1") (pintype "passive"))
      (node (ref "C11") (pin "1") (pinfunction "1_1") (pintype "passive"))
      (node (ref "C12") (pin "1") (pinfunction "1_1") (pintype "passive"))
      (node (ref "C2") (pin "1") (pinfunction "1_1") (pintype "passive"))
      (node (ref "C3") (pin "1") (pinfunction "1_1") (pintype "passive"))
      (node (ref "C4") (pin "1") (pinfunction "1_1") (pintype "passive"))
      (node (ref "C5") (pin "1") (pinfunction "1_1") (pintype "passive"))
      (node (ref "C6") (pin "1") (pinfunction "1_1") (pintype "passive"))
      (node (ref "C7") (pin "1") (pinfunction "1_1") (pintype "passive"))
      (node (ref "C8") (pin "1") (pinfunction "1_1") (pintype "passive"))
      (node (ref "C9") (pin "2") (pinfunction "1_2") (pintype "passive"))
      (node (ref "J1") (pin "4") (pinfunction "ID_4") (pintype "passive"))
      (node (ref "J1") (pin "5") (pinfunction "GND_5") (pintype "passive"))
      (node (ref "J1") (pin "MOUNT") (pinfunction "MOUNT_MOUNT") (pintype "passive"))
      (node (ref "J3") (pin "3") (pinfunction "GND_3") (pintype "passive"))
      (node (ref "J3") (pin "5") (pinfunction "GND_5") (pintype "passive"))
      (node (ref "J3") (pin "9") (pinfunction "GND_DETECT_9") (pintype "passive"))
      (node (ref "J4") (pin "5") (pinfunction "GND_5") (pintype "passive"))
      (node (ref "P16") (pin "1") (pinfunction "1_1") (pintype "passive"))
      (node (ref "P7") (pin "1") (pinfunction "1_1") (pintype "passive"))
      (node (ref "Q1") (pin "2") (pinfunction "S_2") (pintype "passive"))
      (node (ref "R2") (pin "1") (pinfunction "1_1") (pintype "passive"))
      (node (ref "R7") (pin "1") (pinfunction "1_1") (pintype "passive"))
      (node (ref "R8") (pin "1") (pinfunction "1_1") (pintype "passive"))
      (node (ref "RESET1") (pin "1") (pinfunction "1_1") (pintype "passive"))
      (node (ref "U10") (pin "2") (pinfunction "GND_2") (pintype "passive"))
      (node (ref "U2") (pin "2") (pinfunction "VSS_2") (pintype "passive"))
      (node (ref "U3") (pin "2") (pinfunction "VSS_2") (pintype "passive"))
      (node (ref "U4") (pin "1") (pinfunction "GND_1") (pintype "passive"))
      (node (ref "U5") (pin "B1") (pinfunction "USB0_VSS_B1") (pintype "passive"))
      (node (ref "U5") (pin "B13") (pinfunction "VSS3_B13") (pintype "passive"))
      (node (ref "U5") (pin "B5") (pinfunction "VSS1_B5") (pintype "passive"))
      (node (ref "U5") (pin "B9") (pinfunction "VSS2_B9") (pintype "passive"))
      (node (ref "U5") (pin "H1") (pinfunction "VREFN_H1") (pintype "passive"))
      (node (ref "U5") (pin "H2") (pinfunction "VSSA_H2") (pintype "passive"))
      (node (ref "U5") (pin "M11") (pinfunction "VSS_PMU_M11") (pintype "passive"))
      (node (ref "U5") (pin "M12") (pinfunction "VSS_DCDC0_M12") (pintype "passive"))
      (node (ref "U5") (pin "N1") (pinfunction "VSS0_N1") (pintype "passive"))
      (node (ref "U5") (pin "N12") (pinfunction "VSS_DCDC1_N12") (pintype "passive"))
      (node (ref "U5") (pin "N5") (pinfunction "USB1_VSS_N5") (pintype "passive"))
      (node (ref "U6") (pin "2") (pinfunction "SELECT_2") (pintype "passive"))
      (node (ref "U6") (pin "3") (pinfunction "GND_3") (pintype "passive"))
      (node (ref "U7") (pin "1") (pinfunction "GND_1") (pintype "passive"))
      (node (ref "U7") (pin "12") (pinfunction "GND_12") (pintype "passive"))
      (node (ref "U7") (pin "5") (pinfunction "GND_5") (pintype "passive"))
      (node (ref "U7") (pin "6") (pinfunction "GND_6") (pintype "passive"))
    )
    (net (code "37") (name "Net-(D1-K)") (class "Default")
      (node (ref "D1") (pin "2") (pinfunction "K_2") (pintype "passive"))
      (node (ref "L1") (pin "2") (pinfunction "2_2") (pintype "passive"))
      (node (ref "R1") (pin "1") (pinfunction "1_1") (pintype "passive"))
      (node (ref "U2") (pin "4") (pinfunction "VDD_4") (pintype "passive"))
    )
    (net (code "38") (name "Net-(Q1-D)") (class "Default")
      (node (ref "Q1") (pin "3") (pinfunction "D_3") (pintype "passive"))
      (node (ref "R10") (pin "1") (pinfunction "1_1") (pintype "passive"))
    )
    (net (code "39") (name "Net-(U2-PROG)") (class "Default")
      (node (ref "R8") (pin "2") (pinfunction "2_2") (pintype "passive"))
      (node (ref "U2") (pin "5") (pinfunction "PROG_5") (pintype "passive"))
    )
    (net (code "40") (name "Net-(U5-FB)") (class "Default")
      (node (ref "C7") (pin "2") (pinfunction "1_2") (pintype "passive"))
      (node (ref "C8") (pin "2") (pinfunction "1_2") (pintype "passive"))
      (node (ref "L2") (pin "1") (pinfunction "1_1") (pintype "passive"))
      (node (ref "U5") (pin "M9") (pinfunction "VDD_PMU_M9") (pintype "passive"))
      (node (ref "U5") (pin "N9") (pinfunction "FB_N9") (pintype "passive"))
    )
    (net (code "41") (name "Net-(U5-LX)") (class "Default")
      (node (ref "L2") (pin "2") (pinfunction "2_2") (pintype "passive"))
      (node (ref "U5") (pin "N11") (pinfunction "LX_N11") (pintype "passive"))
    )
    (net (code "42") (name "Net-(U5-RESETN)") (class "Default")
      (node (ref "R5") (pin "1") (pinfunction "1_1") (pintype "passive"))
      (node (ref "RESET1") (pin "2") (pinfunction "2_2") (pintype "passive"))
      (node (ref "U5") (pin "J6") (pinfunction "RESETN_J6") (pintype "passive"))
    )
    (net (code "43") (name "Net-(U5-USB0_DM)") (class "Default")
      (node (ref "R3") (pin "2") (pinfunction "2_2") (pintype "passive"))
      (node (ref "U5") (pin "A1") (pinfunction "USB0_DM_A1") (pintype "passive"))
    )
    (net (code "44") (name "Net-(U5-USB0_DP)") (class "Default")
      (node (ref "R4") (pin "2") (pinfunction "2_2") (pintype "passive"))
      (node (ref "U5") (pin "A2") (pinfunction "USB0_DP_A2") (pintype "passive"))
    )
    (net (code "45") (name "Net-(U5-VDDA)") (class "Default")
      (node (ref "C9") (pin "1") (pinfunction "1_1") (pintype "passive"))
      (node (ref "L3") (pin "2") (pinfunction "2_2") (pintype "passive"))
      (node (ref "U5") (pin "G2") (pinfunction "VDDA_G2") (pintype "passive"))
    )
    (net (code "46") (name "Net-(U5-VREFP)") (class "Default")
      (node (ref "C10") (pin "2") (pinfunction "1_2") (pintype "passive"))
      (node (ref "L4") (pin "2") (pinfunction "2_2") (pintype "passive"))
      (node (ref "U5") (pin "G1") (pinfunction "VREFP_G1") (pintype "passive"))
    )
    (net (code "47") (name "Net-(U5-XTAL32M_N)") (class "Default")
      (node (ref "C12") (pin "2") (pinfunction "1_2") (pintype "passive"))
      (node (ref "U5") (pin "M3") (pinfunction "XTAL32M_N_M3") (pintype "passive"))
      (node (ref "U9") (pin "1") (pinfunction "OSC1_1") (pintype "passive"))
    )
    (net (code "48") (name "Net-(U5-XTAL32M_P)") (class "Default")
      (node (ref "C11") (pin "2") (pinfunction "1_2") (pintype "passive"))
      (node (ref "U5") (pin "N3") (pinfunction "XTAL32M_P_N3") (pintype "passive"))
      (node (ref "U9") (pin "2") (pinfunction "OSC2_2") (pintype "passive"))
    )
    (net (code "49") (name "Net-(U7-LEDK)") (class "Default")
      (node (ref "R10") (pin "2") (pinfunction "2_2") (pintype "passive"))
      (node (ref "U7") (pin "2") (pinfunction "LEDK_2") (pintype "passive"))
    )
    (net (code "50") (name "Net-(U10-+)") (class "Default")
      (node (ref "P9") (pin "1") (pinfunction "1_1") (pintype "passive"))
      (node (ref "R7") (pin "2") (pinfunction "2_2") (pintype "passive"))
      (node (ref "U10") (pin "3") (pinfunction "+_3") (pintype "passive"))
    )
    (net (code "51") (name "VBATT") (class "Default")
      (node (ref "U2") (pin "3") (pinfunction "VBAT_3") (pintype "passive"))
      (node (ref "U3") (pin "1") (pinfunction "VIN_1") (pintype "passive"))
      (node (ref "U3") (pin "3") (pinfunction "~{SHDN}_3") (pintype "passive"))
    )
    (net (code "52") (name "unconnected-(BTN1-SHIELD-PadS)") (class "Default")
      (node (ref "BTN1") (pin "S") (pinfunction "SHIELD_S") (pintype "passive"))
    )
    (net (code "53") (name "unconnected-(BTN2-SHIELD-PadS)") (class "Default")
      (node (ref "BTN2") (pin "S") (pinfunction "SHIELD_S") (pintype "passive"))
    )
    (net (code "54") (name "unconnected-(BTN3-SHIELD-PadS)") (class "Default")
      (node (ref "BTN3") (pin "S") (pinfunction "SHIELD_S") (pintype "passive"))
    )
    (net (code "55") (name "unconnected-(J3-KEY-Pad7)") (class "Default")
      (node (ref "J3") (pin "7") (pinfunction "KEY_7") (pintype "passive+no_connect"))
    )
    (net (code "56") (name "unconnected-(J3-TDI-Pad8)") (class "Default")
      (node (ref "J3") (pin "8") (pinfunction "TDI_8") (pintype "passive+no_connect"))
    )
    (net (code "57") (name "unconnected-(RESET1-SHIELD-PadS)") (class "Default")
      (node (ref "RESET1") (pin "S") (pinfunction "SHIELD_S") (pintype "passive"))
    )
    (net (code "58") (name "unconnected-(U3-NC-Pad4)") (class "Default")
      (node (ref "U3") (pin "4") (pinfunction "NC_4") (pintype "passive"))
    )
    (net (code "59") (name "unconnected-(U5-PIO0_0{slash}FC3_SCK{slash}CTIMER0_MAT0{slash}SCT_GPI0{slash}SD1_CARD_INT_N{slash}SECURE_GPIO0_0{slash}ACMP0_A-PadL12)") (class "Default")
      (node (ref "U5") (pin "L12") (pinfunction "PIO0_0/FC3_SCK/CTIMER0_MAT0/SCT_GPI0/SD1_CARD_INT_N/SECURE_GPIO0_0/ACMP0_A_L12") (pintype "passive+no_connect"))
    )
    (net (code "60") (name "unconnected-(U5-PIO0_1{slash}FC3_CTS_SDA_SSEL0{slash}CT_INP0{slash}SCT_GPI1{slash}SD1_CLK{slash}CMP0_OUT{slash}SECURE_GPIO0_1-PadF5)") (class "Default")
      (node (ref "U5") (pin "F5") (pinfunction "PIO0_1/FC3_CTS_SDA_SSEL0/CT_INP0/SCT_GPI1/SD1_CLK/CMP0_OUT/SECURE_GPIO0_1_F5") (pintype "passive+no_connect"))
    )
    (net (code "61") (name "unconnected-(U5-PIO0_4{slash}FC4_SCK{slash}CT_INP12{slash}SCT_GPI4{slash}FC3_CTS_SDA_SSEL0{slash}SECURE_GPIO0_4-PadE7)") (class "Default")
      (node (ref "U5") (pin "E7") (pinfunction "PIO0_4/FC4_SCK/CT_INP12/SCT_GPI4/FC3_CTS_SDA_SSEL0/SECURE_GPIO0_4_E7") (pintype "passive+no_connect"))
    )
    (net (code "62") (name "unconnected-(U5-PIO0_7{slash}FC3_RTS_SCL_SSEL1{slash}SD0_CLK{slash}FC5_SCK{slash}FC1_SCK{slash}SECURE_GPIO0_7-PadG5)") (class "Default")
      (node (ref "U5") (pin "G5") (pinfunction "PIO0_7/FC3_RTS_SCL_SSEL1/SD0_CLK/FC5_SCK/FC1_SCK/SECURE_GPIO0_7_G5") (pintype "passive+no_connect"))
    )
    (net (code "63") (name "unconnected-(U5-PIO0_8{slash}FC3_SSEL3{slash}SD0_CMD{slash}FC5_RXD_SDA_MOSI_DATA{slash}SWO{slash}SECURE_GPIO0_8-PadM2)") (class "Default")
      (node (ref "U5") (pin "M2") (pinfunction "PIO0_8/FC3_SSEL3/SD0_CMD/FC5_RXD_SDA_MOSI_DATA/SWO/SECURE_GPIO0_8_M2") (pintype "passive+no_connect"))
    )
    (net (code "64") (name "unconnected-(U5-PIO0_9{slash}FC3_SSEL2{slash}SD0_POW_EN{slash}FC5_TXD_SCL_MISO_WS{slash}SECURE_GPIO0_9{slash}ACMP0_B-PadL13)") (class "Default")
      (node (ref "U5") (pin "L13") (pinfunction "PIO0_9/FC3_SSEL2/SD0_POW_EN/FC5_TXD_SCL_MISO_WS/SECURE_GPIO0_9/ACMP0_B_L13") (pintype "passive+no_connect"))
    )
    (net (code "65") (name "unconnected-(U5-PIO0_17{slash}FC4_SSEL2{slash}SD0_CARD_DET_N{slash}SCT_GPI7{slash}SCT0_OUT0{slash}SD0_CARD_INT_N{slash}PLU_IN2{slash}SECURE_GPIO0_17-PadG3)") (class "Default")
      (node (ref "U5") (pin "G3") (pinfunction "PIO0_17/FC4_SSEL2/SD0_CARD_DET_N/SCT_GPI7/SCT0_OUT0/SD0_CARD_INT_N/PLU_IN2/SECURE_GPIO0_17_G3") (pintype "passive+no_connect"))
    )
    (net (code "66") (name "unconnected-(U5-PIO0_18{slash}FC4_CTS_SDA_SSEL0{slash}SD0_WR_PRT{slash}CTIMER1_MAT0{slash}SCT0_OUT1{slash}PLU_IN3{slash}SECURE_GPIO0_18{slash}ACMP0_C-PadH9)") (class "Default")
      (node (ref "U5") (pin "H9") (pinfunction "PIO0_18/FC4_CTS_SDA_SSEL0/SD0_WR_PRT/CTIMER1_MAT0/SCT0_OUT1/PLU_IN3/SECURE_GPIO0_18/ACMP0_C_H9") (pintype "passive+no_connect"))
    )
    (net (code "67") (name "unconnected-(U5-PIO0_19{slash}FC4_RTS_SCL_SSEL1{slash}UTICK_CAP0{slash}CTIMER0_MAT2{slash}SCT0_OUT2{slash}FC7_TXD_SCL_MISO_WS{slash}PLU_IN4{slash}SECURE_GPIO0_19-PadE6)") (class "Default")
      (node (ref "U5") (pin "E6") (pinfunction "PIO0_19/FC4_RTS_SCL_SSEL1/UTICK_CAP0/CTIMER0_MAT2/SCT0_OUT2/FC7_TXD_SCL_MISO_WS/PLU_IN4/SECURE_GPIO0_19_E6") (pintype "passive+no_connect"))
    )
    (net (code "68") (name "unconnected-(U5-PIO0_21{slash}FC3_RTS_SCL_SSEL1{slash}UTICK_CAP3{slash}CTIMER3_MAT3{slash}SCT_GPI3{slash}FC7_SCK{slash}PLU_CLKIN{slash}SECURE_GPIO0_21-PadA12)") (class "Default")
      (node (ref "U5") (pin "A12") (pinfunction "PIO0_21/FC3_RTS_SCL_SSEL1/UTICK_CAP3/CTIMER3_MAT3/SCT_GPI3/FC7_SCK/PLU_CLKIN/SECURE_GPIO0_21_A12") (pintype "passive+no_connect"))
    )
    (net (code "69") (name "unconnected-(U5-PIO0_25{slash}FC0_TXD_SCL_MISO_WS{slash}SD0_D1{slash}CT_INP9{slash}SCT_GPI1{slash}SECURE_GPIO0_25-PadA11)") (class "Default")
      (node (ref "U5") (pin "A11") (pinfunction "PIO0_25/FC0_TXD_SCL_MISO_WS/SD0_D1/CT_INP9/SCT_GPI1/SECURE_GPIO0_25_A11") (pintype "passive+no_connect"))
    )
    (net (code "70") (name "unconnected-(U5-PIO0_29{slash}FC0_RXD_SDA_MOSI_DATA{slash}SD1_D[2]{slash}CTIMER2_MAT3{slash}SCT0_OUT8{slash}CMP0_OUT{slash}PLU_OUT2{slash}SEC_PIO0_29-PadH8)") (class "Default")
      (node (ref "U5") (pin "H8") (pinfunction "PIO0_29/FC0_RXD_SDA_MOSI_DATA/SD1_D[2]/CTIMER2_MAT3/SCT0_OUT8/CMP0_OUT/PLU_OUT2/SEC_PIO0_29_H8") (pintype "passive+no_connect"))
    )
    (net (code "71") (name "unconnected-(U5-PIO0_30{slash}FC0_TXD_SCL_MISO_WS{slash}SD1_D[3]{slash}CTIMER0_MAT0{slash}SCT0_OUT9-PadE5)") (class "Default")
      (node (ref "U5") (pin "E5") (pinfunction "PIO0_30/FC0_TXD_SCL_MISO_WS/SD1_D[3]/CTIMER0_MAT0/SCT0_OUT9_E5") (pintype "passive+no_connect"))
    )
    (net (code "72") (name "unconnected-(U5-PIO1_0{slash}FC0_RTS_SCL_SSEL1{slash}SD0_D3{slash}CT_INP2{slash}SCT_GPI4{slash}PLU_OUT3{slash}ADC0_11-PadE1)") (class "Default")
      (node (ref "U5") (pin "E1") (pinfunction "PIO1_0/FC0_RTS_SCL_SSEL1/SD0_D3/CT_INP2/SCT_GPI4/PLU_OUT3/ADC0_11_E1") (pintype "passive+no_connect"))
    )
    (net (code "73") (name "unconnected-(U5-PIO1_6{slash}FC0_TXD_SCL_MISO_WS{slash}SD0_D3{slash}CTIMER2_MAT1{slash}SCT_GPI3-PadH5)") (class "Default")
      (node (ref "U5") (pin "H5") (pinfunction "PIO1_6/FC0_TXD_SCL_MISO_WS/SD0_D3/CTIMER2_MAT1/SCT_GPI3_H5") (pintype "passive+no_connect"))
    )
    (net (code "74") (name "unconnected-(U5-PIO1_7{slash}FC0_RTS_SCL_SSEL1{slash}SD0_D1{slash}CTIMER2_MAT2{slash}SCT_GPI4-PadJ5)") (class "Default")
      (node (ref "U5") (pin "J5") (pinfunction "PIO1_7/FC0_RTS_SCL_SSEL1/SD0_D1/CTIMER2_MAT2/SCT_GPI4_J5") (pintype "passive+no_connect"))
    )
    (net (code "75") (name "unconnected-(U5-PIO1_8{slash}FC0_CTS_SDA_SSEL0{slash}SD0_CLK{slash}SCT0_OUT1{slash}FC4_SSEL2{slash}ADC0_4-PadA6)") (class "Default")
      (node (ref "U5") (pin "A6") (pinfunction "PIO1_8/FC0_CTS_SDA_SSEL0/SD0_CLK/SCT0_OUT1/FC4_SSEL2/ADC0_4_A6") (pintype "passive+no_connect"))
    )
    (net (code "76") (name "unconnected-(U5-PIO1_10{slash}FC1_RXD_SDA_MOSI_DATA{slash}CTIMER1_MAT0{slash}SCT0_OUT3-PadJ7)") (class "Default")
      (node (ref "U5") (pin "J7") (pinfunction "PIO1_10/FC1_RXD_SDA_MOSI_DATA/CTIMER1_MAT0/SCT0_OUT3_J7") (pintype "passive+no_connect"))
    )
    (net (code "77") (name "unconnected-(U5-PIO1_11{slash}FC1_TXD_SCL_MISO_WS{slash}CT_INP5{slash}USB0_VBUS-PadG6)") (class "Default")
      (node (ref "U5") (pin "G6") (pinfunction "PIO1_11/FC1_TXD_SCL_MISO_WS/CT_INP5/USB0_VBUS_G6") (pintype "passive+no_connect"))
    )
    (net (code "78") (name "unconnected-(U5-PIO1_13{slash}FC6_RXD_SDA_MOSI_DATA{slash}CT_INP6{slash}USB0_OVERCURRENTN{slash}USB0_FRAME{slash}SD0_CARD_DET_N-PadB3)") (class "Default")
      (node (ref "U5") (pin "B3") (pinfunction "PIO1_13/FC6_RXD_SDA_MOSI_DATA/CT_INP6/USB0_OVERCURRENTN/USB0_FRAME/SD0_CARD_DET_N_B3") (pintype "passive+no_connect"))
    )
    (net (code "79") (name "unconnected-(U5-PIO1_14{slash}UTICK_CAP2{slash}CTIMER1_MAT2{slash}FC5_CTS_SDA_SSEL0{slash}USB0_LEDN{slash}SD1_CMD{slash}ACMP0_D-PadL7)") (class "Default")
      (node (ref "U5") (pin "L7") (pinfunction "PIO1_14/UTICK_CAP2/CTIMER1_MAT2/FC5_CTS_SDA_SSEL0/USB0_LEDN/SD1_CMD/ACMP0_D_L7") (pintype "passive+no_connect"))
    )
    (net (code "80") (name "unconnected-(U5-PIO1_15{slash}UTICK_CAP3{slash}CT_INP7{slash}FC5_RTS_SCL_SSEL1{slash}FC4_RTS_SCL_SSEL1{slash}SD1_D2-PadB6)") (class "Default")
      (node (ref "U5") (pin "B6") (pinfunction "PIO1_15/UTICK_CAP3/CT_INP7/FC5_RTS_SCL_SSEL1/FC4_RTS_SCL_SSEL1/SD1_D2_B6") (pintype "passive+no_connect"))
    )
    (net (code "81") (name "unconnected-(U5-PIO1_16{slash}FC6_TXD_SCL_MISO_WS{slash}CTIMER1_MAT3{slash}SD0_CMD-PadC7)") (class "Default")
      (node (ref "U5") (pin "C7") (pinfunction "PIO1_16/FC6_TXD_SCL_MISO_WS/CTIMER1_MAT3/SD0_CMD_C7") (pintype "passive+no_connect"))
    )
    (net (code "82") (name "unconnected-(U5-PIO1_17{slash}FC6_RTS_SCL_SSEL1{slash}SCT0_OUT4{slash}SD1_CARD_INT_N{slash}SD1_CARD_DET_N-PadJ9)") (class "Default")
      (node (ref "U5") (pin "J9") (pinfunction "PIO1_17/FC6_RTS_SCL_SSEL1/SCT0_OUT4/SD1_CARD_INT_N/SD1_CARD_DET_N_J9") (pintype "passive+no_connect"))
    )
    (net (code "83") (name "unconnected-(U5-PIO1_18{slash}SD1_POW_EN{slash}SCT0_OUT5{slash}PLU_OUT0-PadG9)") (class "Default")
      (node (ref "U5") (pin "G9") (pinfunction "PIO1_18/SD1_POW_EN/SCT0_OUT5/PLU_OUT0_G9") (pintype "passive+no_connect"))
    )
    (net (code "84") (name "unconnected-(U5-PIO1_20{slash}FC7_RTS_SCL_SSEL1{slash}CT_INP14{slash}FC4_TXD_SCL_MISO_WS{slash}PLU_OUT2-PadC2)") (class "Default")
      (node (ref "U5") (pin "C2") (pinfunction "PIO1_20/FC7_RTS_SCL_SSEL1/CT_INP14/FC4_TXD_SCL_MISO_WS/PLU_OUT2_C2") (pintype "passive+no_connect"))
    )
    (net (code "85") (name "unconnected-(U5-PIO1_21{slash}FC7_CTS_SDA_SSEL0{slash}CTIMER3_MAT2{slash}FC4_RXD_SDA_MOSI_DATA{slash}PLU_OUT3-PadM7)") (class "Default")
      (node (ref "U5") (pin "M7") (pinfunction "PIO1_21/FC7_CTS_SDA_SSEL0/CTIMER3_MAT2/FC4_RXD_SDA_MOSI_DATA/PLU_OUT3_M7") (pintype "passive+no_connect"))
    )
    (net (code "86") (name "unconnected-(U5-PIO1_23{slash}FC2_SCK{slash}SCT0_OUT0{slash}SD1_D3{slash}FC3_SSEL2{slash}PLU_OUT5-PadJ8)") (class "Default")
      (node (ref "U5") (pin "J8") (pinfunction "PIO1_23/FC2_SCK/SCT0_OUT0/SD1_D3/FC3_SSEL2/PLU_OUT5_J8") (pintype "passive+no_connect"))
    )
    (net (code "87") (name "unconnected-(U5-PIO1_24{slash}FC2_RXD_SDA_MOSI_DATA{slash}SCT0_OUT1{slash}SD1_D1{slash}FC3_SSEL3{slash}PLU_OUT6-PadF6)") (class "Default")
      (node (ref "U5") (pin "F6") (pinfunction "PIO1_24/FC2_RXD_SDA_MOSI_DATA/SCT0_OUT1/SD1_D1/FC3_SSEL3/PLU_OUT6_F6") (pintype "passive+no_connect"))
    )
    (net (code "88") (name "unconnected-(U5-PIO1_25{slash}FC2_TXD_SCL_MISO_WS{slash}SCT0_OUT2{slash}SD1_D0{slash}UTICK_CAP0{slash}PLU_CLKIN-PadB8)") (class "Default")
      (node (ref "U5") (pin "B8") (pinfunction "PIO1_25/FC2_TXD_SCL_MISO_WS/SCT0_OUT2/SD1_D0/UTICK_CAP0/PLU_CLKIN_B8") (pintype "passive+no_connect"))
    )
    (net (code "89") (name "unconnected-(U5-PIO1_27{slash}FC2_RTS_SCL_SSEL1{slash}SD0_D4{slash}CTIMER0_MAT3{slash}CLKOUT{slash}PLU_IN4-PadE8)") (class "Default")
      (node (ref "U5") (pin "E8") (pinfunction "PIO1_27/FC2_RTS_SCL_SSEL1/SD0_D4/CTIMER0_MAT3/CLKOUT/PLU_IN4_E8") (pintype "passive+no_connect"))
    )
    (net (code "90") (name "unconnected-(U5-PIO1_28{slash}FC7_SCK{slash}SD0_D5{slash}CT_INP2{slash}PLU_IN3-PadA8)") (class "Default")
      (node (ref "U5") (pin "A8") (pinfunction "PIO1_28/FC7_SCK/SD0_D5/CT_INP2/PLU_IN3_A8") (pintype "passive+no_connect"))
    )
    (net (code "91") (name "unconnected-(U5-PIO1_29{slash}FC7_RXD_SDA_MOSI_DATA{slash}SD0_D6{slash}SCT_GPI6{slash}USB1_PORTPWRN{slash}USB1_FRAME{slash}PLU_IN2-PadG8)") (class "Default")
      (node (ref "U5") (pin "G8") (pinfunction "PIO1_29/FC7_RXD_SDA_MOSI_DATA/SD0_D6/SCT_GPI6/USB1_PORTPWRN/USB1_FRAME/PLU_IN2_G8") (pintype "passive+no_connect"))
    )
    (net (code "92") (name "unconnected-(U5-PIO1_30{slash}FC7_TXD_SCL_MISO_WS{slash}SD0_D7{slash}SCT_GPI7{slash}USB1_OVERCURRENTN{slash}USB1_LEDN{slash}PLU_IN1-PadF9)") (class "Default")
      (node (ref "U5") (pin "F9") (pinfunction "PIO1_30/FC7_TXD_SCL_MISO_WS/SD0_D7/SCT_GPI7/USB1_OVERCURRENTN/USB1_LEDN/PLU_IN1_F9") (pintype "passive+no_connect"))
    )
    (net (code "93") (name "unconnected-(U5-PIO1_31{slash}MCLK{slash}SD1_CLK{slash}CTIMER0_MAT2{slash}SCT0_OUT6{slash}PLU_IN0-PadH6)") (class "Default")
      (node (ref "U5") (pin "H6") (pinfunction "PIO1_31/MCLK/SD1_CLK/CTIMER0_MAT2/SCT0_OUT6/PLU_IN0_H6") (pintype "passive+no_connect"))
    )
    (net (code "94") (name "unconnected-(U5-USB1_3V3-PadN7)") (class "Default")
      (node (ref "U5") (pin "N7") (pinfunction "USB1_3V3_N7") (pintype "passive+no_connect"))
    )
    (net (code "95") (name "unconnected-(U5-USB1_DM-PadN6)") (class "Default")
      (node (ref "U5") (pin "N6") (pinfunction "USB1_DM_N6") (pintype "passive+no_connect"))
    )
    (net (code "96") (name "unconnected-(U5-USB1_DP-PadM6)") (class "Default")
      (node (ref "U5") (pin "M6") (pinfunction "USB1_DP_M6") (pintype "passive+no_connect"))
    )
    (net (code "97") (name "unconnected-(U5-USB1_VBUS-PadN8)") (class "Default")
      (node (ref "U5") (pin "N8") (pinfunction "USB1_VBUS_N8") (pintype "passive+no_connect"))
    )
    (net (code "98") (name "unconnected-(U5-XTAL32K_N-PadJ12)") (class "Default")
      (node (ref "U5") (pin "J12") (pinfunction "XTAL32K_N_J12") (pintype "passive"))
    )
    (net (code "99") (name "unconnected-(U5-XTAL32K_P-PadJ13)") (class "Default")
      (node (ref "U5") (pin "J13") (pinfunction "XTAL32K_P_J13") (pintype "passive"))
    )
  )
)
